# Access_System_Bmduino_V1_0.net
KiCad netlist of a schematic drawn in Altium Designer
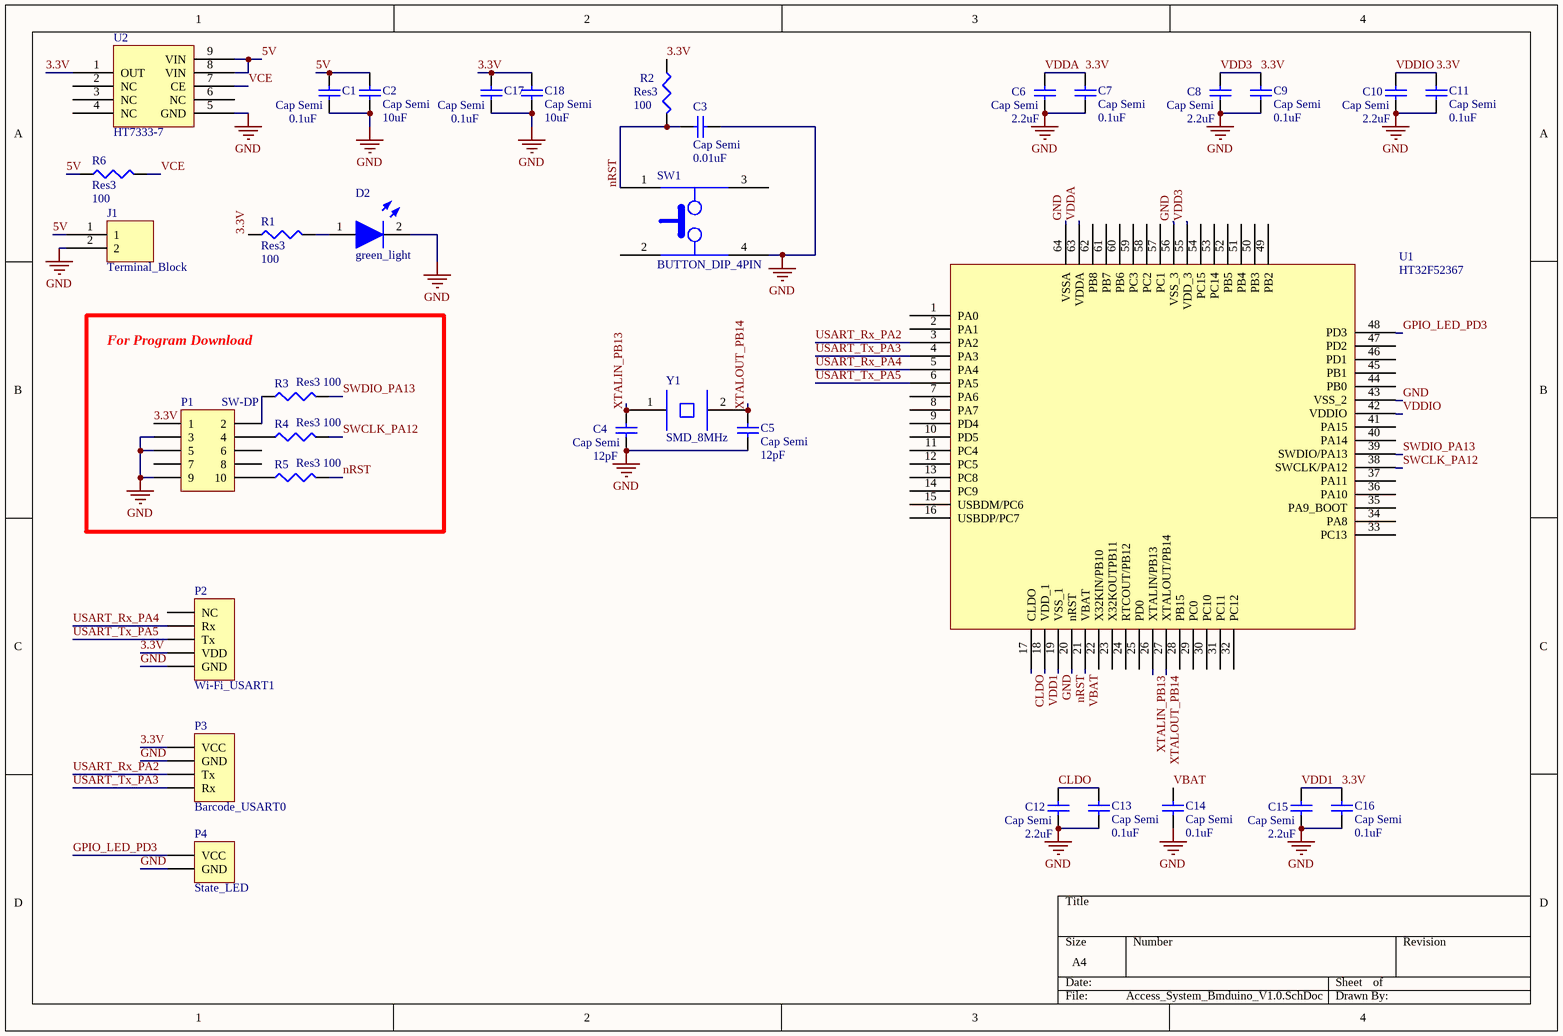
[diagram p0: Access_System_Bmduino_V1.0.SchDoc]

(export (version "E")
  (design (tool "Eeschema 10.0.6"))
  (components
    (comp (ref "C1")
      (value "Cap Semi")
      (footprint "1608[0603]")
      (description "Capacitor (Semiconductor SIM Model)")
      (fields (field (name "ALTIUM_VALUE") "0.1uF") (field (name "PUBLISHER") "Altium Limited"))
      (libsource (lib "Miscellaneous Devices") (part "Cap Semi"))
    )
    (comp (ref "C2")
      (value "Cap Semi")
      (footprint "1608[0603]")
      (description "Capacitor (Semiconductor SIM Model)")
      (fields (field (name "ALTIUM_VALUE") "10uF") (field (name "PUBLISHER") "Altium Limited"))
      (libsource (lib "Miscellaneous Devices") (part "Cap Semi"))
    )
    (comp (ref "C3")
      (value "Cap Semi")
      (footprint "1608[0603]")
      (description "Capacitor (Semiconductor SIM Model)")
      (fields (field (name "ALTIUM_VALUE") "0.01uF") (field (name "PUBLISHER") "Altium Limited"))
      (libsource (lib "Miscellaneous Devices") (part "Cap Semi"))
    )
    (comp (ref "C4")
      (value "Cap Semi")
      (footprint "1608[0603]")
      (description "Capacitor (Semiconductor SIM Model)")
      (fields (field (name "ALTIUM_VALUE") "12pF") (field (name "PUBLISHER") "Altium Limited"))
      (libsource (lib "Miscellaneous Devices") (part "Cap Semi"))
    )
    (comp (ref "C5")
      (value "Cap Semi")
      (footprint "1608[0603]")
      (description "Capacitor (Semiconductor SIM Model)")
      (fields (field (name "ALTIUM_VALUE") "12pF") (field (name "PUBLISHER") "Altium Limited"))
      (libsource (lib "Miscellaneous Devices") (part "Cap Semi"))
    )
    (comp (ref "C6")
      (value "Cap Semi")
      (footprint "1608[0603]")
      (description "Capacitor (Semiconductor SIM Model)")
      (fields (field (name "ALTIUM_VALUE") "2.2uF") (field (name "PUBLISHER") "Altium Limited"))
      (libsource (lib "Miscellaneous Devices") (part "Cap Semi"))
    )
    (comp (ref "C7")
      (value "Cap Semi")
      (footprint "1608[0603]")
      (description "Capacitor (Semiconductor SIM Model)")
      (fields (field (name "ALTIUM_VALUE") "0.1uF") (field (name "PUBLISHER") "Altium Limited"))
      (libsource (lib "Miscellaneous Devices") (part "Cap Semi"))
    )
    (comp (ref "C8")
      (value "Cap Semi")
      (footprint "1608[0603]")
      (description "Capacitor (Semiconductor SIM Model)")
      (fields (field (name "ALTIUM_VALUE") "2.2uF") (field (name "PUBLISHER") "Altium Limited"))
      (libsource (lib "Miscellaneous Devices") (part "Cap Semi"))
    )
    (comp (ref "C9")
      (value "Cap Semi")
      (footprint "1608[0603]")
      (description "Capacitor (Semiconductor SIM Model)")
      (fields (field (name "ALTIUM_VALUE") "0.1uF") (field (name "PUBLISHER") "Altium Limited"))
      (libsource (lib "Miscellaneous Devices") (part "Cap Semi"))
    )
    (comp (ref "C10")
      (value "Cap Semi")
      (footprint "1608[0603]")
      (description "Capacitor (Semiconductor SIM Model)")
      (fields (field (name "ALTIUM_VALUE") "2.2uF") (field (name "PUBLISHER") "Altium Limited"))
      (libsource (lib "Miscellaneous Devices") (part "Cap Semi"))
    )
    (comp (ref "C11")
      (value "Cap Semi")
      (footprint "1608[0603]")
      (description "Capacitor (Semiconductor SIM Model)")
      (fields (field (name "ALTIUM_VALUE") "0.1uF") (field (name "PUBLISHER") "Altium Limited"))
      (libsource (lib "Miscellaneous Devices") (part "Cap Semi"))
    )
    (comp (ref "C12")
      (value "Cap Semi")
      (footprint "1608[0603]")
      (description "Capacitor (Semiconductor SIM Model)")
      (fields (field (name "ALTIUM_VALUE") "2.2uF") (field (name "PUBLISHER") "Altium Limited"))
      (libsource (lib "Miscellaneous Devices") (part "Cap Semi"))
    )
    (comp (ref "C13")
      (value "Cap Semi")
      (footprint "1608[0603]")
      (description "Capacitor (Semiconductor SIM Model)")
      (fields (field (name "ALTIUM_VALUE") "0.1uF") (field (name "PUBLISHER") "Altium Limited"))
      (libsource (lib "Miscellaneous Devices") (part "Cap Semi"))
    )
    (comp (ref "C14")
      (value "Cap Semi")
      (footprint "1608[0603]")
      (description "Capacitor (Semiconductor SIM Model)")
      (fields (field (name "ALTIUM_VALUE") "0.1uF") (field (name "PUBLISHER") "Altium Limited"))
      (libsource (lib "Miscellaneous Devices") (part "Cap Semi"))
    )
    (comp (ref "C15")
      (value "Cap Semi")
      (footprint "1608[0603]")
      (description "Capacitor (Semiconductor SIM Model)")
      (fields (field (name "ALTIUM_VALUE") "2.2uF") (field (name "PUBLISHER") "Altium Limited"))
      (libsource (lib "Miscellaneous Devices") (part "Cap Semi"))
    )
    (comp (ref "C16")
      (value "Cap Semi")
      (footprint "1608[0603]")
      (description "Capacitor (Semiconductor SIM Model)")
      (fields (field (name "ALTIUM_VALUE") "0.1uF") (field (name "PUBLISHER") "Altium Limited"))
      (libsource (lib "Miscellaneous Devices") (part "Cap Semi"))
    )
    (comp (ref "C17")
      (value "Cap Semi")
      (footprint "1608[0603]")
      (description "Capacitor (Semiconductor SIM Model)")
      (fields (field (name "ALTIUM_VALUE") "0.1uF") (field (name "PUBLISHER") "Altium Limited"))
      (libsource (lib "Miscellaneous Devices") (part "Cap Semi"))
    )
    (comp (ref "C18")
      (value "Cap Semi")
      (footprint "1608[0603]")
      (description "Capacitor (Semiconductor SIM Model)")
      (fields (field (name "ALTIUM_VALUE") "10uF") (field (name "PUBLISHER") "Altium Limited"))
      (libsource (lib "Miscellaneous Devices") (part "Cap Semi"))
    )
    (comp (ref "D2")
      (value "green_light")
      (footprint "LED_Green")
      (libsource (lib "Lab_share") (part "LED_Green"))
    )
    (comp (ref "J1")
      (value "Terminal_Block")
      (footprint "terminal block")
      (libsource (lib "Lab_share") (part "Terminal Block"))
    )
    (comp (ref "P1")
      (value "SW-DP")
      (footprint "HDR2X5")
      (description "Header, 5-Pin, Dual row")
      (fields (field (name "PUBLISHER") "Altium Limited"))
      (libsource (lib "Miscellaneous Connectors") (part "Header 5X2"))
    )
    (comp (ref "P2")
      (value "Wi-Fi_USART1")
      (footprint "HDR1X5")
      (description "Header, 5-Pin")
      (fields (field (name "PUBLISHER") "Altium Limited"))
      (libsource (lib "Miscellaneous Connectors") (part "Header 5"))
    )
    (comp (ref "P3")
      (value "Barcode_USART0")
      (footprint "HDR1X4")
      (description "Header, 4-Pin")
      (fields (field (name "PUBLISHER") "Altium Limited"))
      (libsource (lib "Miscellaneous Connectors") (part "Header 4"))
    )
    (comp (ref "P4")
      (value "State_LED")
      (footprint "HDR1X2")
      (description "Header, 2-Pin")
      (fields (field (name "PUBLISHER") "Altium Limited"))
      (libsource (lib "Miscellaneous Connectors") (part "Header 2"))
    )
    (comp (ref "R1")
      (value "Res3")
      (footprint "J1-0603")
      (description "Resistor")
      (fields (field (name "ALTIUM_VALUE") "100") (field (name "PUBLISHER") "Altium Limited"))
      (libsource (lib "Miscellaneous Devices") (part "Res3"))
    )
    (comp (ref "R2")
      (value "Res3")
      (footprint "J1-0603")
      (description "Resistor")
      (fields (field (name "ALTIUM_VALUE") "100") (field (name "PUBLISHER") "Altium Limited"))
      (libsource (lib "Miscellaneous Devices") (part "Res3"))
    )
    (comp (ref "R3")
      (value "Res3")
      (footprint "J1-0603")
      (description "Resistor")
      (fields (field (name "ALTIUM_VALUE") "100") (field (name "PUBLISHER") "Altium Limited"))
      (libsource (lib "Miscellaneous Devices") (part "Res3"))
    )
    (comp (ref "R4")
      (value "Res3")
      (footprint "J1-0603")
      (description "Resistor")
      (fields (field (name "ALTIUM_VALUE") "100") (field (name "PUBLISHER") "Altium Limited"))
      (libsource (lib "Miscellaneous Devices") (part "Res3"))
    )
    (comp (ref "R5")
      (value "Res3")
      (footprint "J1-0603")
      (description "Resistor")
      (fields (field (name "ALTIUM_VALUE") "100") (field (name "PUBLISHER") "Altium Limited"))
      (libsource (lib "Miscellaneous Devices") (part "Res3"))
    )
    (comp (ref "R6")
      (value "Res3")
      (footprint "J1-0603")
      (description "Resistor")
      (fields (field (name "ALTIUM_VALUE") "100") (field (name "PUBLISHER") "Altium Limited"))
      (libsource (lib "Miscellaneous Devices") (part "Res3"))
    )
    (comp (ref "SW1")
      (value "BUTTON_DIP_4PIN")
      (footprint "Push_Button")
      (libsource (lib "Lab_share") (part "Push_Button"))
    )
    (comp (ref "U1")
      (value "HT32F52367")
      (footprint "HT32H52367")
      (libsource (lib "Lab_share") (part "HT32F52367"))
    )
    (comp (ref "U2") (value "HT7333-7") (footprint "HT7333") (libsource (lib "Lab_share") (part "HT7333")))
    (comp (ref "Y1")
      (value "SMD_8MHz")
      (footprint "Quartz-Crystal-8MHz")
      (libsource (lib "Lab_share") (part "Quartz_Crystal_8MHz"))
    )
  )
  (nets
    (net (code "1") (name "/3.3V") (class "Default")
      (node (ref "C10") (pin "1") (pinfunction "1_1") (pintype "passive"))
      (node (ref "C11") (pin "2") (pinfunction "2_2") (pintype "passive"))
      (node (ref "C15") (pin "1") (pinfunction "1_1") (pintype "passive"))
      (node (ref "C16") (pin "2") (pinfunction "2_2") (pintype "passive"))
      (node (ref "C17") (pin "2") (pinfunction "2_2") (pintype "passive"))
      (node (ref "C18") (pin "2") (pinfunction "2_2") (pintype "passive"))
      (node (ref "C6") (pin "1") (pinfunction "1_1") (pintype "passive"))
      (node (ref "C7") (pin "2") (pinfunction "2_2") (pintype "passive"))
      (node (ref "C8") (pin "1") (pinfunction "1_1") (pintype "passive"))
      (node (ref "C9") (pin "2") (pinfunction "2_2") (pintype "passive"))
      (node (ref "P1") (pin "1") (pinfunction "1_1") (pintype "passive"))
      (node (ref "P2") (pin "4") (pinfunction "VDD_4") (pintype "passive"))
      (node (ref "P3") (pin "1") (pinfunction "VCC_1") (pintype "passive"))
      (node (ref "R1") (pin "1") (pinfunction "1_1") (pintype "passive"))
      (node (ref "R2") (pin "1") (pinfunction "1_1") (pintype "passive"))
      (node (ref "U1") (pin "18") (pinfunction "VDD_1_18") (pintype "passive"))
      (node (ref "U1") (pin "42") (pinfunction "VDDIO_42") (pintype "passive"))
      (node (ref "U1") (pin "55") (pinfunction "VDD_3_55") (pintype "passive"))
      (node (ref "U1") (pin "63") (pinfunction "VDDA_63") (pintype "passive"))
      (node (ref "U2") (pin "1") (pinfunction "OUT_1") (pintype "passive"))
    )
    (net (code "2") (name "/5V") (class "Default")
      (node (ref "C1") (pin "2") (pinfunction "2_2") (pintype "passive"))
      (node (ref "C2") (pin "2") (pinfunction "2_2") (pintype "passive"))
      (node (ref "J1") (pin "1") (pinfunction "1_1") (pintype "passive"))
      (node (ref "R6") (pin "1") (pinfunction "1_1") (pintype "passive"))
      (node (ref "U2") (pin "8") (pinfunction "VIN_8") (pintype "passive"))
      (node (ref "U2") (pin "9") (pinfunction "VIN_9") (pintype "passive"))
    )
    (net (code "3") (name "/CLDO") (class "Default")
      (node (ref "C12") (pin "1") (pinfunction "1_1") (pintype "passive"))
      (node (ref "C13") (pin "2") (pinfunction "2_2") (pintype "passive"))
      (node (ref "U1") (pin "17") (pinfunction "CLDO_17") (pintype "passive"))
    )
    (net (code "4") (name "/GPIO_LED_PD3") (class "Default")
      (node (ref "P4") (pin "1") (pinfunction "VCC_1") (pintype "passive"))
      (node (ref "U1") (pin "48") (pinfunction "PD3_48") (pintype "passive"))
    )
    (net (code "5") (name "/SWCLK_PA12") (class "Default")
      (node (ref "R4") (pin "2") (pinfunction "2_2") (pintype "passive"))
      (node (ref "U1") (pin "38") (pinfunction "SWCLK/PA12_38") (pintype "passive"))
    )
    (net (code "6") (name "/SWDIO_PA13") (class "Default")
      (node (ref "R3") (pin "2") (pinfunction "2_2") (pintype "passive"))
      (node (ref "U1") (pin "39") (pinfunction "SWDIO/PA13_39") (pintype "passive"))
    )
    (net (code "7") (name "/USART_Rx_PA2") (class "Default")
      (node (ref "P3") (pin "3") (pinfunction "Tx_3") (pintype "passive"))
      (node (ref "U1") (pin "3") (pinfunction "PA2_3") (pintype "passive"))
    )
    (net (code "8") (name "/USART_Rx_PA4") (class "Default")
      (node (ref "P2") (pin "2") (pinfunction "Rx_2") (pintype "passive"))
      (node (ref "U1") (pin "5") (pinfunction "PA4_5") (pintype "passive"))
    )
    (net (code "9") (name "/USART_Tx_PA3") (class "Default")
      (node (ref "P3") (pin "4") (pinfunction "Rx_4") (pintype "passive"))
      (node (ref "U1") (pin "4") (pinfunction "PA3_4") (pintype "passive"))
    )
    (net (code "10") (name "/USART_Tx_PA5") (class "Default")
      (node (ref "P2") (pin "3") (pinfunction "Tx_3") (pintype "passive"))
      (node (ref "U1") (pin "6") (pinfunction "PA5_6") (pintype "passive"))
    )
    (net (code "11") (name "/VBAT") (class "Default")
      (node (ref "C14") (pin "2") (pinfunction "2_2") (pintype "passive"))
      (node (ref "U1") (pin "21") (pinfunction "VBAT_21") (pintype "passive"))
    )
    (net (code "12") (name "/VCE") (class "Default")
      (node (ref "R6") (pin "2") (pinfunction "2_2") (pintype "passive"))
      (node (ref "U2") (pin "7") (pinfunction "CE_7") (pintype "passive"))
    )
    (net (code "13") (name "/XTALIN_PB13") (class "Default")
      (node (ref "C4") (pin "1") (pinfunction "1_1") (pintype "passive"))
      (node (ref "U1") (pin "26") (pinfunction "XTALIN/PB13_26") (pintype "passive"))
      (node (ref "Y1") (pin "1") (pintype "passive"))
    )
    (net (code "14") (name "/XTALOUT_PB14") (class "Default")
      (node (ref "C5") (pin "2") (pinfunction "2_2") (pintype "passive"))
      (node (ref "U1") (pin "27") (pinfunction "XTALOUT/PB14_27") (pintype "passive"))
      (node (ref "Y1") (pin "2") (pintype "passive"))
    )
    (net (code "15") (name "/nRST") (class "Default")
      (node (ref "C3") (pin "2") (pinfunction "2_2") (pintype "passive"))
      (node (ref "R2") (pin "2") (pinfunction "2_2") (pintype "passive"))
      (node (ref "R5") (pin "2") (pinfunction "2_2") (pintype "passive"))
      (node (ref "SW1") (pin "1") (pintype "passive"))
      (node (ref "U1") (pin "20") (pinfunction "nRST_20") (pintype "passive"))
    )
    (net (code "16") (name "GND") (class "Default")
      (node (ref "C1") (pin "1") (pinfunction "1_1") (pintype "passive"))
      (node (ref "C10") (pin "2") (pinfunction "2_2") (pintype "passive"))
      (node (ref "C11") (pin "1") (pinfunction "1_1") (pintype "passive"))
      (node (ref "C12") (pin "2") (pinfunction "2_2") (pintype "passive"))
      (node (ref "C13") (pin "1") (pinfunction "1_1") (pintype "passive"))
      (node (ref "C14") (pin "1") (pinfunction "1_1") (pintype "passive"))
      (node (ref "C15") (pin "2") (pinfunction "2_2") (pintype "passive"))
      (node (ref "C16") (pin "1") (pinfunction "1_1") (pintype "passive"))
      (node (ref "C17") (pin "1") (pinfunction "1_1") (pintype "passive"))
      (node (ref "C18") (pin "1") (pinfunction "1_1") (pintype "passive"))
      (node (ref "C2") (pin "1") (pinfunction "1_1") (pintype "passive"))
      (node (ref "C3") (pin "1") (pinfunction "1_1") (pintype "passive"))
      (node (ref "C4") (pin "2") (pinfunction "2_2") (pintype "passive"))
      (node (ref "C5") (pin "1") (pinfunction "1_1") (pintype "passive"))
      (node (ref "C6") (pin "2") (pinfunction "2_2") (pintype "passive"))
      (node (ref "C7") (pin "1") (pinfunction "1_1") (pintype "passive"))
      (node (ref "C8") (pin "2") (pinfunction "2_2") (pintype "passive"))
      (node (ref "C9") (pin "1") (pinfunction "1_1") (pintype "passive"))
      (node (ref "D2") (pin "2") (pintype "passive"))
      (node (ref "J1") (pin "2") (pinfunction "2_2") (pintype "passive"))
      (node (ref "P1") (pin "3") (pinfunction "3_3") (pintype "passive"))
      (node (ref "P1") (pin "5") (pinfunction "5_5") (pintype "passive"))
      (node (ref "P1") (pin "9") (pinfunction "9_9") (pintype "passive"))
      (node (ref "P2") (pin "5") (pinfunction "GND_5") (pintype "passive"))
      (node (ref "P3") (pin "2") (pinfunction "GND_2") (pintype "passive"))
      (node (ref "P4") (pin "2") (pinfunction "GND_2") (pintype "passive"))
      (node (ref "SW1") (pin "4") (pintype "passive"))
      (node (ref "U1") (pin "19") (pinfunction "VSS_1_19") (pintype "passive"))
      (node (ref "U1") (pin "43") (pinfunction "VSS_2_43") (pintype "passive"))
      (node (ref "U1") (pin "56") (pinfunction "VSS_3_56") (pintype "passive"))
      (node (ref "U1") (pin "64") (pinfunction "VSSA_64") (pintype "passive"))
      (node (ref "U2") (pin "5") (pinfunction "GND_5") (pintype "passive"))
    )
    (net (code "17") (name "Net-(D2-Pad1)") (class "Default")
      (node (ref "D2") (pin "1") (pintype "passive"))
      (node (ref "R1") (pin "2") (pinfunction "2_2") (pintype "passive"))
    )
    (net (code "18") (name "Net-(P1-Pad2)") (class "Default")
      (node (ref "P1") (pin "2") (pinfunction "2_2") (pintype "passive"))
      (node (ref "R3") (pin "1") (pinfunction "1_1") (pintype "passive"))
    )
    (net (code "19") (name "Net-(P1-Pad4)") (class "Default")
      (node (ref "P1") (pin "4") (pinfunction "4_4") (pintype "passive"))
      (node (ref "R4") (pin "1") (pinfunction "1_1") (pintype "passive"))
    )
    (net (code "20") (name "Net-(P1-Pad10)") (class "Default")
      (node (ref "P1") (pin "10") (pinfunction "10_10") (pintype "passive"))
      (node (ref "R5") (pin "1") (pinfunction "1_1") (pintype "passive"))
    )
    (net (code "21") (name "unconnected-(P1-Pad6)") (class "Default")
      (node (ref "P1") (pin "6") (pinfunction "6_6") (pintype "passive"))
    )
    (net (code "22") (name "unconnected-(P1-Pad7)") (class "Default")
      (node (ref "P1") (pin "7") (pinfunction "7_7") (pintype "passive"))
    )
    (net (code "23") (name "unconnected-(P1-Pad8)") (class "Default")
      (node (ref "P1") (pin "8") (pinfunction "8_8") (pintype "passive"))
    )
    (net (code "24") (name "unconnected-(P2-NC-Pad1)") (class "Default")
      (node (ref "P2") (pin "1") (pinfunction "NC_1") (pintype "passive"))
    )
    (net (code "25") (name "unconnected-(SW1-Pad2)") (class "Default")
      (node (ref "SW1") (pin "2") (pintype "passive"))
    )
    (net (code "26") (name "unconnected-(SW1-Pad3)") (class "Default")
      (node (ref "SW1") (pin "3") (pintype "passive"))
    )
    (net (code "27") (name "unconnected-(U1-PA0-Pad1)") (class "Default")
      (node (ref "U1") (pin "1") (pinfunction "PA0_1") (pintype "passive"))
    )
    (net (code "28") (name "unconnected-(U1-PA1-Pad2)") (class "Default")
      (node (ref "U1") (pin "2") (pinfunction "PA1_2") (pintype "passive"))
    )
    (net (code "29") (name "unconnected-(U1-PA6-Pad7)") (class "Default")
      (node (ref "U1") (pin "7") (pinfunction "PA6_7") (pintype "passive"))
    )
    (net (code "30") (name "unconnected-(U1-PA7-Pad8)") (class "Default")
      (node (ref "U1") (pin "8") (pinfunction "PA7_8") (pintype "passive"))
    )
    (net (code "31") (name "unconnected-(U1-PA8-Pad34)") (class "Default")
      (node (ref "U1") (pin "34") (pinfunction "PA8_34") (pintype "passive"))
    )
    (net (code "32") (name "unconnected-(U1-PA9_BOOT-Pad35)") (class "Default")
      (node (ref "U1") (pin "35") (pinfunction "PA9_BOOT_35") (pintype "passive"))
    )
    (net (code "33") (name "unconnected-(U1-PA10-Pad36)") (class "Default")
      (node (ref "U1") (pin "36") (pinfunction "PA10_36") (pintype "passive"))
    )
    (net (code "34") (name "unconnected-(U1-PA11-Pad37)") (class "Default")
      (node (ref "U1") (pin "37") (pinfunction "PA11_37") (pintype "passive"))
    )
    (net (code "35") (name "unconnected-(U1-PA14-Pad40)") (class "Default")
      (node (ref "U1") (pin "40") (pinfunction "PA14_40") (pintype "passive"))
    )
    (net (code "36") (name "unconnected-(U1-PA15-Pad41)") (class "Default")
      (node (ref "U1") (pin "41") (pinfunction "PA15_41") (pintype "passive"))
    )
    (net (code "37") (name "unconnected-(U1-PB0-Pad44)") (class "Default")
      (node (ref "U1") (pin "44") (pinfunction "PB0_44") (pintype "passive"))
    )
    (net (code "38") (name "unconnected-(U1-PB1-Pad45)") (class "Default")
      (node (ref "U1") (pin "45") (pinfunction "PB1_45") (pintype "passive"))
    )
    (net (code "39") (name "unconnected-(U1-PB2-Pad49)") (class "Default")
      (node (ref "U1") (pin "49") (pinfunction "PB2_49") (pintype "passive"))
    )
    (net (code "40") (name "unconnected-(U1-PB3-Pad50)") (class "Default")
      (node (ref "U1") (pin "50") (pinfunction "PB3_50") (pintype "passive"))
    )
    (net (code "41") (name "unconnected-(U1-PB4-Pad51)") (class "Default")
      (node (ref "U1") (pin "51") (pinfunction "PB4_51") (pintype "passive"))
    )
    (net (code "42") (name "unconnected-(U1-PB5-Pad52)") (class "Default")
      (node (ref "U1") (pin "52") (pinfunction "PB5_52") (pintype "passive"))
    )
    (net (code "43") (name "unconnected-(U1-PB6-Pad60)") (class "Default")
      (node (ref "U1") (pin "60") (pinfunction "PB6_60") (pintype "passive"))
    )
    (net (code "44") (name "unconnected-(U1-PB7-Pad61)") (class "Default")
      (node (ref "U1") (pin "61") (pinfunction "PB7_61") (pintype "passive"))
    )
    (net (code "45") (name "unconnected-(U1-PB8-Pad62)") (class "Default")
      (node (ref "U1") (pin "62") (pinfunction "PB8_62") (pintype "passive"))
    )
    (net (code "46") (name "unconnected-(U1-PB15-Pad28)") (class "Default")
      (node (ref "U1") (pin "28") (pinfunction "PB15_28") (pintype "passive"))
    )
    (net (code "47") (name "unconnected-(U1-PC0-Pad29)") (class "Default")
      (node (ref "U1") (pin "29") (pinfunction "PC0_29") (pintype "passive"))
    )
    (net (code "48") (name "unconnected-(U1-PC1-Pad57)") (class "Default")
      (node (ref "U1") (pin "57") (pinfunction "PC1_57") (pintype "passive"))
    )
    (net (code "49") (name "unconnected-(U1-PC2-Pad58)") (class "Default")
      (node (ref "U1") (pin "58") (pinfunction "PC2_58") (pintype "passive"))
    )
    (net (code "50") (name "unconnected-(U1-PC3-Pad59)") (class "Default")
      (node (ref "U1") (pin "59") (pinfunction "PC3_59") (pintype "passive"))
    )
    (net (code "51") (name "unconnected-(U1-PC4-Pad11)") (class "Default")
      (node (ref "U1") (pin "11") (pinfunction "PC4_11") (pintype "passive"))
    )
    (net (code "52") (name "unconnected-(U1-PC5-Pad12)") (class "Default")
      (node (ref "U1") (pin "12") (pinfunction "PC5_12") (pintype "passive"))
    )
    (net (code "53") (name "unconnected-(U1-PC8-Pad13)") (class "Default")
      (node (ref "U1") (pin "13") (pinfunction "PC8_13") (pintype "passive"))
    )
    (net (code "54") (name "unconnected-(U1-PC9-Pad14)") (class "Default")
      (node (ref "U1") (pin "14") (pinfunction "PC9_14") (pintype "passive"))
    )
    (net (code "55") (name "unconnected-(U1-PC10-Pad30)") (class "Default")
      (node (ref "U1") (pin "30") (pinfunction "PC10_30") (pintype "passive"))
    )
    (net (code "56") (name "unconnected-(U1-PC11-Pad31)") (class "Default")
      (node (ref "U1") (pin "31") (pinfunction "PC11_31") (pintype "passive"))
    )
    (net (code "57") (name "unconnected-(U1-PC12-Pad32)") (class "Default")
      (node (ref "U1") (pin "32") (pinfunction "PC12_32") (pintype "passive"))
    )
    (net (code "58") (name "unconnected-(U1-PC13-Pad33)") (class "Default")
      (node (ref "U1") (pin "33") (pinfunction "PC13_33") (pintype "passive"))
    )
    (net (code "59") (name "unconnected-(U1-PC14-Pad53)") (class "Default")
      (node (ref "U1") (pin "53") (pinfunction "PC14_53") (pintype "passive"))
    )
    (net (code "60") (name "unconnected-(U1-PC15-Pad54)") (class "Default")
      (node (ref "U1") (pin "54") (pinfunction "PC15_54") (pintype "passive"))
    )
    (net (code "61") (name "unconnected-(U1-PD0-Pad25)") (class "Default")
      (node (ref "U1") (pin "25") (pinfunction "PD0_25") (pintype "passive"))
    )
    (net (code "62") (name "unconnected-(U1-PD1-Pad46)") (class "Default")
      (node (ref "U1") (pin "46") (pinfunction "PD1_46") (pintype "passive"))
    )
    (net (code "63") (name "unconnected-(U1-PD2-Pad47)") (class "Default")
      (node (ref "U1") (pin "47") (pinfunction "PD2_47") (pintype "passive"))
    )
    (net (code "64") (name "unconnected-(U1-PD4-Pad9)") (class "Default")
      (node (ref "U1") (pin "9") (pinfunction "PD4_9") (pintype "passive"))
    )
    (net (code "65") (name "unconnected-(U1-PD5-Pad10)") (class "Default")
      (node (ref "U1") (pin "10") (pinfunction "PD5_10") (pintype "passive"))
    )
    (net (code "66") (name "unconnected-(U1-RTCOUT{slash}PB12-Pad24)") (class "Default")
      (node (ref "U1") (pin "24") (pinfunction "RTCOUT/PB12_24") (pintype "passive"))
    )
    (net (code "67") (name "unconnected-(U1-USBDM{slash}PC6-Pad15)") (class "Default")
      (node (ref "U1") (pin "15") (pinfunction "USBDM/PC6_15") (pintype "passive"))
    )
    (net (code "68") (name "unconnected-(U1-USBDP{slash}PC7-Pad16)") (class "Default")
      (node (ref "U1") (pin "16") (pinfunction "USBDP/PC7_16") (pintype "passive"))
    )
    (net (code "69") (name "unconnected-(U1-X32KIN{slash}PB10-Pad22)") (class "Default")
      (node (ref "U1") (pin "22") (pinfunction "X32KIN/PB10_22") (pintype "passive"))
    )
    (net (code "70") (name "unconnected-(U1-X32KOUTPB11-Pad23)") (class "Default")
      (node (ref "U1") (pin "23") (pinfunction "X32KOUTPB11_23") (pintype "passive"))
    )
    (net (code "71") (name "unconnected-(U2-NC-Pad2)") (class "Default")
      (node (ref "U2") (pin "2") (pinfunction "NC_2") (pintype "passive"))
    )
    (net (code "72") (name "unconnected-(U2-NC-Pad3)") (class "Default")
      (node (ref "U2") (pin "3") (pinfunction "NC_3") (pintype "passive"))
    )
    (net (code "73") (name "unconnected-(U2-NC-Pad4)") (class "Default")
      (node (ref "U2") (pin "4") (pinfunction "NC_4") (pintype "passive"))
    )
    (net (code "74") (name "unconnected-(U2-NC-Pad6)") (class "Default")
      (node (ref "U2") (pin "6") (pinfunction "NC_6") (pintype "passive"))
    )
  )
)
